# 3_mcu.net
KiCad netlist of a schematic drawn in Altium Designer
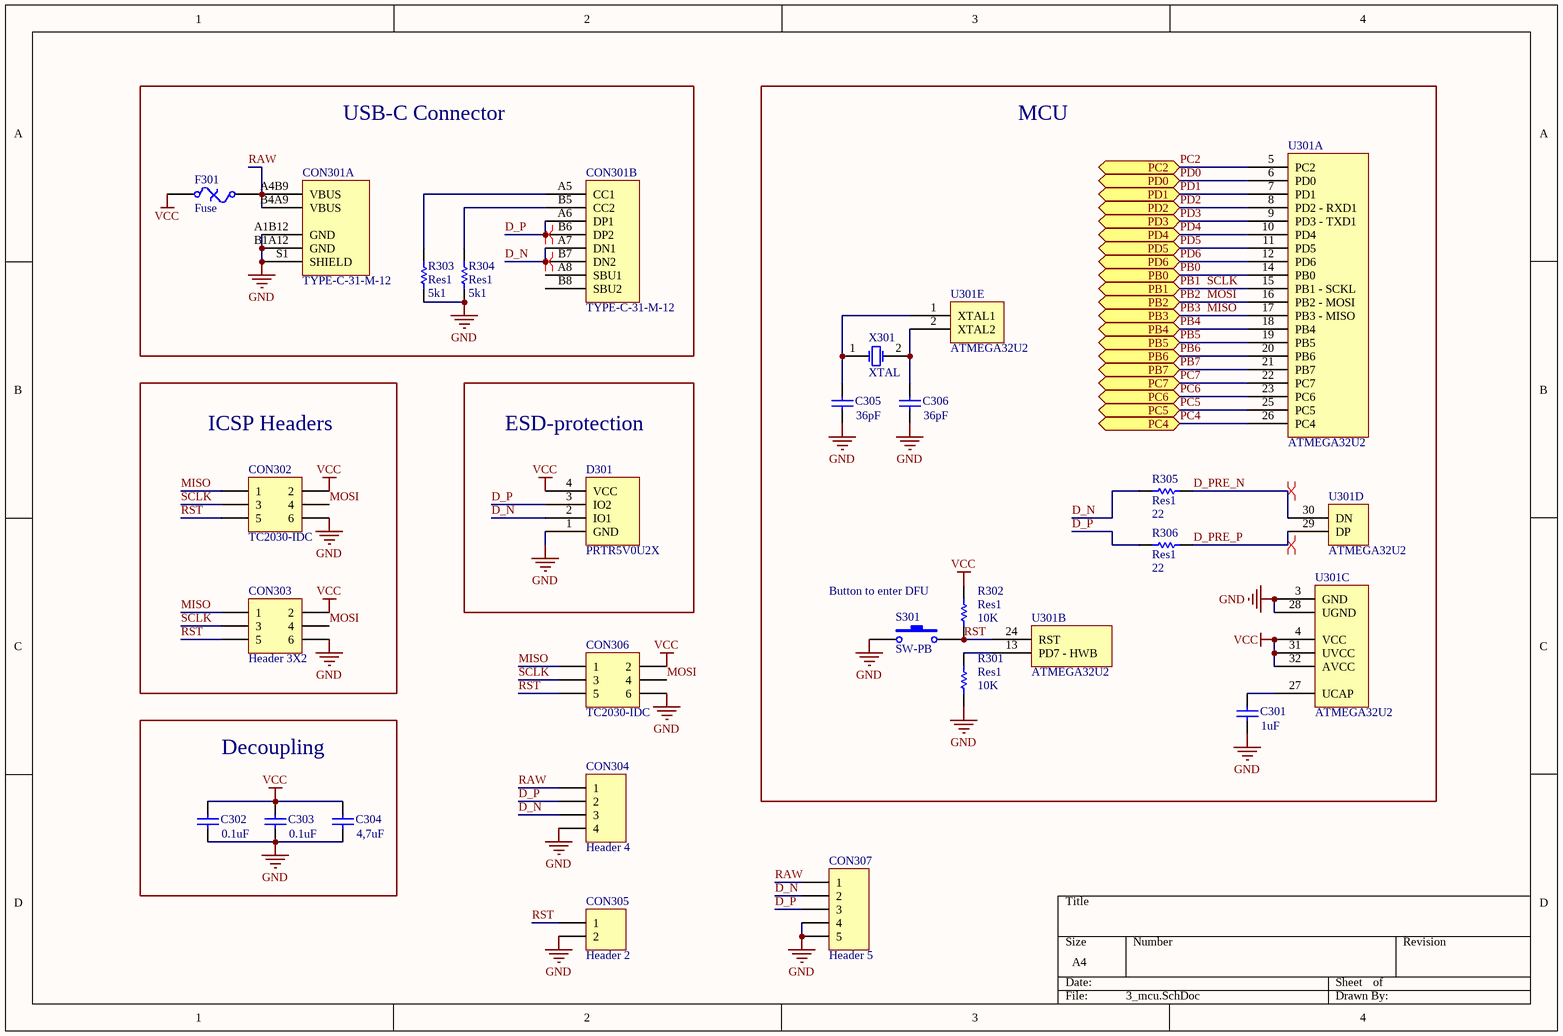
[diagram p0: 3_mcu.SchDoc]

(export (version "E")
  (design (tool "Eeschema 10.0.6"))
  (components
    (comp (ref "C301")
      (value "1uF")
      (footprint "C0603[1608]")
      (description "Capacitor")
      (fields (field (name "MFG") "KEMET") (field (name "MRF.PART") "CL10A105KB8NNNC"))
      (libsource (lib "Miscellaneous Devices") (part "Cap"))
    )
    (comp (ref "C302")
      (value "0.1uF")
      (footprint "C0603[1608]")
      (description "Capacitor")
      (fields (field (name "MFG") "KEMET") (field (name "MRF.PART") "CC0603KRX7R9BB104"))
      (libsource (lib "Miscellaneous Devices") (part "Cap"))
    )
    (comp (ref "C303")
      (value "0.1uF")
      (footprint "C0603[1608]")
      (description "Capacitor")
      (fields (field (name "MFG") "KEMET") (field (name "MRF.PART") "CC0603KRX7R9BB104"))
      (libsource (lib "Miscellaneous Devices") (part "Cap"))
    )
    (comp (ref "C304")
      (value "4,7uF")
      (footprint "C1206[3216]")
      (description "Capacitor")
      (fields (field (name "MFG") "KEMET") (field (name "MRF.PART") "1206B475K500NT"))
      (libsource (lib "Miscellaneous Devices") (part "Cap"))
    )
    (comp (ref "C305")
      (value "36pF")
      (footprint "C0603[1608]")
      (description "Capacitor")
      (fields (field (name "MFG") "KEMET") (field (name "MRF.PART") "CL10C360JB8NNNC"))
      (libsource (lib "Miscellaneous Devices") (part "Cap"))
    )
    (comp (ref "C306")
      (value "36pF")
      (footprint "C0603[1608]")
      (description "Capacitor")
      (fields (field (name "MFG") "KEMET") (field (name "MRF.PART") "CL10C360JB8NNNC"))
      (libsource (lib "Miscellaneous Devices") (part "Cap"))
    )
    (comp (ref "CON301")
      (value "TYPE-C-31-M-12")
      (footprint "TYPE-C-31-M-12")
      (fields (field (name "MFG") "Korean Hroparts Elec"))
      (libsource (lib "Keebs") (part "TYPE-C-31-M-12"))
    )
    (comp (ref "CON302")
      (value "TC2030-IDC")
      (footprint "TC2030-IDC-NL")
      (description "Header, 3-Pin, Dual row")
      (libsource (lib "Miscellaneous Connectors") (part "Header 3X2"))
    )
    (comp (ref "CON303")
      (value "Header 3X2")
      (footprint "HDR2X3")
      (description "Header, 3-Pin, Dual row")
      (libsource (lib "Miscellaneous Connectors") (part "Header 3X2"))
    )
    (comp (ref "CON304")
      (value "Header 4")
      (footprint "HDR1X4")
      (description "Header, 4-Pin")
      (libsource (lib "Miscellaneous Connectors") (part "Header 4"))
    )
    (comp (ref "CON305")
      (value "Header 2")
      (footprint "HDR1X2")
      (description "Header, 2-Pin")
      (libsource (lib "Miscellaneous Connectors") (part "Header 2"))
    )
    (comp (ref "CON306")
      (value "TC2030-IDC")
      (footprint "TC2030-IDC-NL")
      (description "Header, 3-Pin, Dual row")
      (libsource (lib "Miscellaneous Connectors") (part "Header 3X2"))
    )
    (comp (ref "CON307")
      (value "Header 5")
      (footprint "JST SM04B-SRSS-TB")
      (description "Header, 5-Pin")
      (fields (field (name "MFG") "JST Sales America Inc."))
      (libsource (lib "Miscellaneous Connectors") (part "Header 5"))
    )
    (comp (ref "D301")
      (value "PRTR5V0U2X")
      (footprint "SOT190P237X120-4N")
      (fields (field (name "MFG") "Nexperia USA Inc.") (field (name "MRF.PART") "UET14A05L03"))
      (libsource (lib "Keebs") (part "PRTR5V0U2X"))
    )
    (comp (ref "F301")
      (value "Fuse")
      (footprint "C1206[3216]")
      (description "Thermal Fuse")
      (fields (field (name "MFG") "Bel Fuse Inc.") (field (name "MRF.PART") "ASMD1206-050"))
      (libsource (lib "Miscellaneous Devices") (part "Fuse Thermal"))
    )
    (comp (ref "R301")
      (value "Res1")
      (footprint "R0603[1608]")
      (description "Resistor")
      (fields
        (field (name "ALTIUM_VALUE") "10K")
        (field (name "MFG") "Panasonic Electronic Components")
        (field (name "MRF.PART") "0603WAF1002T5E")
      )
      (libsource (lib "Miscellaneous Devices") (part "Res1"))
    )
    (comp (ref "R302")
      (value "Res1")
      (footprint "R0603[1608]")
      (description "Resistor")
      (fields
        (field (name "ALTIUM_VALUE") "10K")
        (field (name "MFG") "Panasonic Electronic Components")
        (field (name "MRF.PART") "0603WAF1002T5E")
      )
      (libsource (lib "Miscellaneous Devices") (part "Res1"))
    )
    (comp (ref "R303")
      (value "Res1")
      (footprint "R0603[1608]")
      (description "Resistor")
      (fields
        (field (name "ALTIUM_VALUE") "5k1")
        (field (name "MFG") "Panasonic Electronic Components")
        (field (name "MRF.PART") "0603WAF5101T5E")
      )
      (libsource (lib "Miscellaneous Devices") (part "Res1"))
    )
    (comp (ref "R304")
      (value "Res1")
      (footprint "R0603[1608]")
      (description "Resistor")
      (fields
        (field (name "ALTIUM_VALUE") "5k1")
        (field (name "MFG") "Panasonic Electronic Components")
        (field (name "MRF.PART") "0603WAF5101T5E")
      )
      (libsource (lib "Miscellaneous Devices") (part "Res1"))
    )
    (comp (ref "R305")
      (value "Res1")
      (footprint "R0603[1608]")
      (description "Resistor")
      (fields
        (field (name "ALTIUM_VALUE") "22")
        (field (name "MFG") "Panasonic Electronic Components")
        (field (name "MRF.PART") "0603WAF220JT5E")
      )
      (libsource (lib "Miscellaneous Devices") (part "Res1"))
    )
    (comp (ref "R306")
      (value "Res1")
      (footprint "R0603[1608]")
      (description "Resistor")
      (fields
        (field (name "ALTIUM_VALUE") "22")
        (field (name "MFG") "Panasonic Electronic Components")
        (field (name "MRF.PART") "0603WAF220JT5E")
      )
      (libsource (lib "Miscellaneous Devices") (part "Res1"))
    )
    (comp (ref "S301")
      (value "SW-PB")
      (footprint "430152050826")
      (description "Switch")
      (fields (field (name "MFG") "C&K") (field (name "MRF.PART") "TS-1187A-C-D-B"))
      (libsource (lib "Miscellaneous Devices") (part "SW-PB"))
    )
    (comp (ref "U301")
      (value "ATMEGA32U2")
      (footprint "ATMEGA32U2-COMBO")
      (fields (field (name "MFG") "Microchip Technology") (field (name "MRF.PART") "ATMEGA32U2-MU"))
      (libsource (lib "Keebs") (part "ATMEGA32U2"))
    )
    (comp (ref "X301")
      (value "XTAL")
      (footprint "CTS 445-series crystal")
      (description "Crystal Oscillator")
      (fields (field (name "MRF.PART") "X503216MSB2GI"))
      (libsource (lib "Miscellaneous Devices") (part "XTAL"))
    )
  )
  (nets
    (net (code "1") (name "/D_N") (class "Default")
      (node (ref "CON301") (pin "A7") (pinfunction "DN1_A7") (pintype "passive"))
      (node (ref "CON301") (pin "B7") (pinfunction "DN2_B7") (pintype "passive"))
      (node (ref "CON304") (pin "3") (pinfunction "3_3") (pintype "passive"))
      (node (ref "CON307") (pin "2") (pinfunction "2_2") (pintype "passive"))
      (node (ref "D301") (pin "2") (pinfunction "IO1_2") (pintype "passive"))
      (node (ref "R305") (pin "2") (pinfunction "2_2") (pintype "passive"))
    )
    (net (code "2") (name "/D_P") (class "Default")
      (node (ref "CON301") (pin "A6") (pinfunction "DP1_A6") (pintype "passive"))
      (node (ref "CON301") (pin "B6") (pinfunction "DP2_B6") (pintype "passive"))
      (node (ref "CON304") (pin "2") (pinfunction "2_2") (pintype "passive"))
      (node (ref "CON307") (pin "3") (pinfunction "3_3") (pintype "passive"))
      (node (ref "D301") (pin "3") (pinfunction "IO2_3") (pintype "passive"))
      (node (ref "R306") (pin "2") (pinfunction "2_2") (pintype "passive"))
    )
    (net (code "3") (name "/D_PRE_N") (class "Default")
      (node (ref "R305") (pin "1") (pinfunction "1_1") (pintype "passive"))
      (node (ref "U301") (pin "30") (pinfunction "DN_30") (pintype "passive"))
    )
    (net (code "4") (name "/D_PRE_P") (class "Default")
      (node (ref "R306") (pin "1") (pinfunction "1_1") (pintype "passive"))
      (node (ref "U301") (pin "29") (pinfunction "DP_29") (pintype "passive"))
    )
    (net (code "5") (name "/MISO") (class "Default")
      (node (ref "CON302") (pin "1") (pinfunction "1_1") (pintype "passive"))
      (node (ref "CON303") (pin "1") (pinfunction "1_1") (pintype "passive"))
      (node (ref "CON306") (pin "1") (pinfunction "1_1") (pintype "passive"))
      (node (ref "U301") (pin "17") (pinfunction "PB3_-_MISO_17") (pintype "passive"))
    )
    (net (code "6") (name "/MOSI") (class "Default")
      (node (ref "CON302") (pin "4") (pinfunction "4_4") (pintype "passive"))
      (node (ref "CON303") (pin "4") (pinfunction "4_4") (pintype "passive"))
      (node (ref "CON306") (pin "4") (pinfunction "4_4") (pintype "passive"))
      (node (ref "U301") (pin "16") (pinfunction "PB2_-_MOSI_16") (pintype "passive"))
    )
    (net (code "7") (name "/PB0") (class "Default")
      (node (ref "U301") (pin "14") (pinfunction "PB0_14") (pintype "passive"))
    )
    (net (code "8") (name "/PB1") (class "Default")
      (node (ref "CON302") (pin "3") (pinfunction "3_3") (pintype "passive"))
      (node (ref "CON303") (pin "3") (pinfunction "3_3") (pintype "passive"))
      (node (ref "CON306") (pin "3") (pinfunction "3_3") (pintype "passive"))
      (node (ref "U301") (pin "15") (pinfunction "PB1_-_SCKL_15") (pintype "passive"))
    )
    (net (code "9") (name "/PB4") (class "Default")
      (node (ref "U301") (pin "18") (pinfunction "PB4_18") (pintype "passive"))
    )
    (net (code "10") (name "/PB5") (class "Default")
      (node (ref "U301") (pin "19") (pinfunction "PB5_19") (pintype "passive"))
    )
    (net (code "11") (name "/PB6") (class "Default")
      (node (ref "U301") (pin "20") (pinfunction "PB6_20") (pintype "passive"))
    )
    (net (code "12") (name "/PB7") (class "Default")
      (node (ref "U301") (pin "21") (pinfunction "PB7_21") (pintype "passive"))
    )
    (net (code "13") (name "/PC2") (class "Default")
      (node (ref "U301") (pin "5") (pinfunction "PC2_5") (pintype "passive"))
    )
    (net (code "14") (name "/PC4") (class "Default")
      (node (ref "U301") (pin "26") (pinfunction "PC4_26") (pintype "passive"))
    )
    (net (code "15") (name "/PC5") (class "Default")
      (node (ref "U301") (pin "25") (pinfunction "PC5_25") (pintype "passive"))
    )
    (net (code "16") (name "/PC6") (class "Default")
      (node (ref "U301") (pin "23") (pinfunction "PC6_23") (pintype "passive"))
    )
    (net (code "17") (name "/PC7") (class "Default")
      (node (ref "U301") (pin "22") (pinfunction "PC7_22") (pintype "passive"))
    )
    (net (code "18") (name "/PD0") (class "Default")
      (node (ref "U301") (pin "6") (pinfunction "PD0_6") (pintype "passive"))
    )
    (net (code "19") (name "/PD1") (class "Default")
      (node (ref "U301") (pin "7") (pinfunction "PD1_7") (pintype "passive"))
    )
    (net (code "20") (name "/PD2") (class "Default")
      (node (ref "U301") (pin "8") (pinfunction "PD2_-_RXD1_8") (pintype "passive"))
    )
    (net (code "21") (name "/PD3") (class "Default")
      (node (ref "U301") (pin "9") (pinfunction "PD3_-_TXD1_9") (pintype "passive"))
    )
    (net (code "22") (name "/PD4") (class "Default")
      (node (ref "U301") (pin "10") (pinfunction "PD4_10") (pintype "passive"))
    )
    (net (code "23") (name "/PD5") (class "Default")
      (node (ref "U301") (pin "11") (pinfunction "PD5_11") (pintype "passive"))
    )
    (net (code "24") (name "/PD6") (class "Default")
      (node (ref "U301") (pin "12") (pinfunction "PD6_12") (pintype "passive"))
    )
    (net (code "25") (name "/RAW") (class "Default")
      (node (ref "CON301") (pin "A4B9") (pinfunction "VBUS_A4B9") (pintype "passive"))
      (node (ref "CON301") (pin "B4A9") (pinfunction "VBUS_B4A9") (pintype "passive"))
      (node (ref "CON304") (pin "1") (pinfunction "1_1") (pintype "passive"))
      (node (ref "CON307") (pin "1") (pinfunction "1_1") (pintype "passive"))
      (node (ref "F301") (pin "2") (pinfunction "2_2") (pintype "passive"))
    )
    (net (code "26") (name "/RST") (class "Default")
      (node (ref "CON302") (pin "5") (pinfunction "5_5") (pintype "passive"))
      (node (ref "CON303") (pin "5") (pinfunction "5_5") (pintype "passive"))
      (node (ref "CON305") (pin "1") (pinfunction "1_1") (pintype "passive"))
      (node (ref "CON306") (pin "5") (pinfunction "5_5") (pintype "passive"))
      (node (ref "R302") (pin "2") (pinfunction "2_2") (pintype "passive"))
      (node (ref "S301") (pin "1") (pinfunction "1_1") (pintype "passive"))
      (node (ref "U301") (pin "24") (pinfunction "RST_24") (pintype "passive"))
    )
    (net (code "27") (name "GND") (class "Default")
      (node (ref "C301") (pin "1") (pinfunction "1_1") (pintype "passive"))
      (node (ref "C302") (pin "1") (pinfunction "1_1") (pintype "passive"))
      (node (ref "C303") (pin "1") (pinfunction "1_1") (pintype "passive"))
      (node (ref "C304") (pin "1") (pinfunction "1_1") (pintype "passive"))
      (node (ref "C305") (pin "1") (pinfunction "1_1") (pintype "passive"))
      (node (ref "C306") (pin "1") (pinfunction "1_1") (pintype "passive"))
      (node (ref "CON301") (pin "A1B12") (pinfunction "GND_A1B12") (pintype "passive"))
      (node (ref "CON301") (pin "B1A12") (pinfunction "GND_B1A12") (pintype "passive"))
      (node (ref "CON301") (pin "S1") (pinfunction "SHIELD_S1") (pintype "passive"))
      (node (ref "CON302") (pin "6") (pinfunction "6_6") (pintype "passive"))
      (node (ref "CON303") (pin "6") (pinfunction "6_6") (pintype "passive"))
      (node (ref "CON304") (pin "4") (pinfunction "4_4") (pintype "passive"))
      (node (ref "CON305") (pin "2") (pinfunction "2_2") (pintype "passive"))
      (node (ref "CON306") (pin "6") (pinfunction "6_6") (pintype "passive"))
      (node (ref "CON307") (pin "4") (pinfunction "4_4") (pintype "passive"))
      (node (ref "CON307") (pin "5") (pinfunction "5_5") (pintype "passive"))
      (node (ref "D301") (pin "1") (pinfunction "GND_1") (pintype "passive"))
      (node (ref "R301") (pin "2") (pinfunction "2_2") (pintype "passive"))
      (node (ref "R303") (pin "2") (pinfunction "2_2") (pintype "passive"))
      (node (ref "R304") (pin "2") (pinfunction "2_2") (pintype "passive"))
      (node (ref "S301") (pin "2") (pinfunction "2_2") (pintype "passive"))
      (node (ref "U301") (pin "28") (pinfunction "UGND_28") (pintype "passive"))
      (node (ref "U301") (pin "3") (pinfunction "GND_3") (pintype "passive"))
    )
    (net (code "28") (name "Net-(CON301B-CC1)") (class "Default")
      (node (ref "CON301") (pin "A5") (pinfunction "CC1_A5") (pintype "passive"))
      (node (ref "R303") (pin "1") (pinfunction "1_1") (pintype "passive"))
    )
    (net (code "29") (name "Net-(CON301B-CC2)") (class "Default")
      (node (ref "CON301") (pin "B5") (pinfunction "CC2_B5") (pintype "passive"))
      (node (ref "R304") (pin "1") (pinfunction "1_1") (pintype "passive"))
    )
    (net (code "30") (name "Net-(U301B-PD7_-_HWB)") (class "Default")
      (node (ref "R301") (pin "1") (pinfunction "1_1") (pintype "passive"))
      (node (ref "U301") (pin "13") (pinfunction "PD7_-_HWB_13") (pintype "passive"))
    )
    (net (code "31") (name "Net-(U301C-UCAP)") (class "Default")
      (node (ref "C301") (pin "2") (pinfunction "2_2") (pintype "passive"))
      (node (ref "U301") (pin "27") (pinfunction "UCAP_27") (pintype "passive"))
    )
    (net (code "32") (name "Net-(U301E-XTAL1)") (class "Default")
      (node (ref "C305") (pin "2") (pinfunction "2_2") (pintype "passive"))
      (node (ref "U301") (pin "1") (pinfunction "XTAL1_1") (pintype "passive"))
      (node (ref "X301") (pin "1") (pinfunction "OSC1_1") (pintype "passive"))
    )
    (net (code "33") (name "Net-(U301E-XTAL2)") (class "Default")
      (node (ref "C306") (pin "2") (pinfunction "2_2") (pintype "passive"))
      (node (ref "U301") (pin "2") (pinfunction "XTAL2_2") (pintype "passive"))
      (node (ref "X301") (pin "2") (pinfunction "OSC2_2") (pintype "passive"))
    )
    (net (code "34") (name "VCC") (class "Default")
      (node (ref "C302") (pin "2") (pinfunction "2_2") (pintype "passive"))
      (node (ref "C303") (pin "2") (pinfunction "2_2") (pintype "passive"))
      (node (ref "C304") (pin "2") (pinfunction "2_2") (pintype "passive"))
      (node (ref "CON302") (pin "2") (pinfunction "2_2") (pintype "passive"))
      (node (ref "CON303") (pin "2") (pinfunction "2_2") (pintype "passive"))
      (node (ref "CON306") (pin "2") (pinfunction "2_2") (pintype "passive"))
      (node (ref "D301") (pin "4") (pinfunction "VCC_4") (pintype "passive"))
      (node (ref "F301") (pin "1") (pinfunction "1_1") (pintype "passive"))
      (node (ref "R302") (pin "1") (pinfunction "1_1") (pintype "passive"))
      (node (ref "U301") (pin "31") (pinfunction "UVCC_31") (pintype "passive"))
      (node (ref "U301") (pin "32") (pinfunction "AVCC_32") (pintype "passive"))
      (node (ref "U301") (pin "4") (pinfunction "VCC_4") (pintype "passive"))
    )
    (net (code "35") (name "unconnected-(CON301B-SBU1-PadA8)") (class "Default")
      (node (ref "CON301") (pin "A8") (pinfunction "SBU1_A8") (pintype "passive"))
    )
    (net (code "36") (name "unconnected-(CON301B-SBU2-PadB8)") (class "Default")
      (node (ref "CON301") (pin "B8") (pinfunction "SBU2_B8") (pintype "passive"))
    )
  )
)
